# D_INPUT.net
KiCad netlist of a schematic drawn in Altium Designer
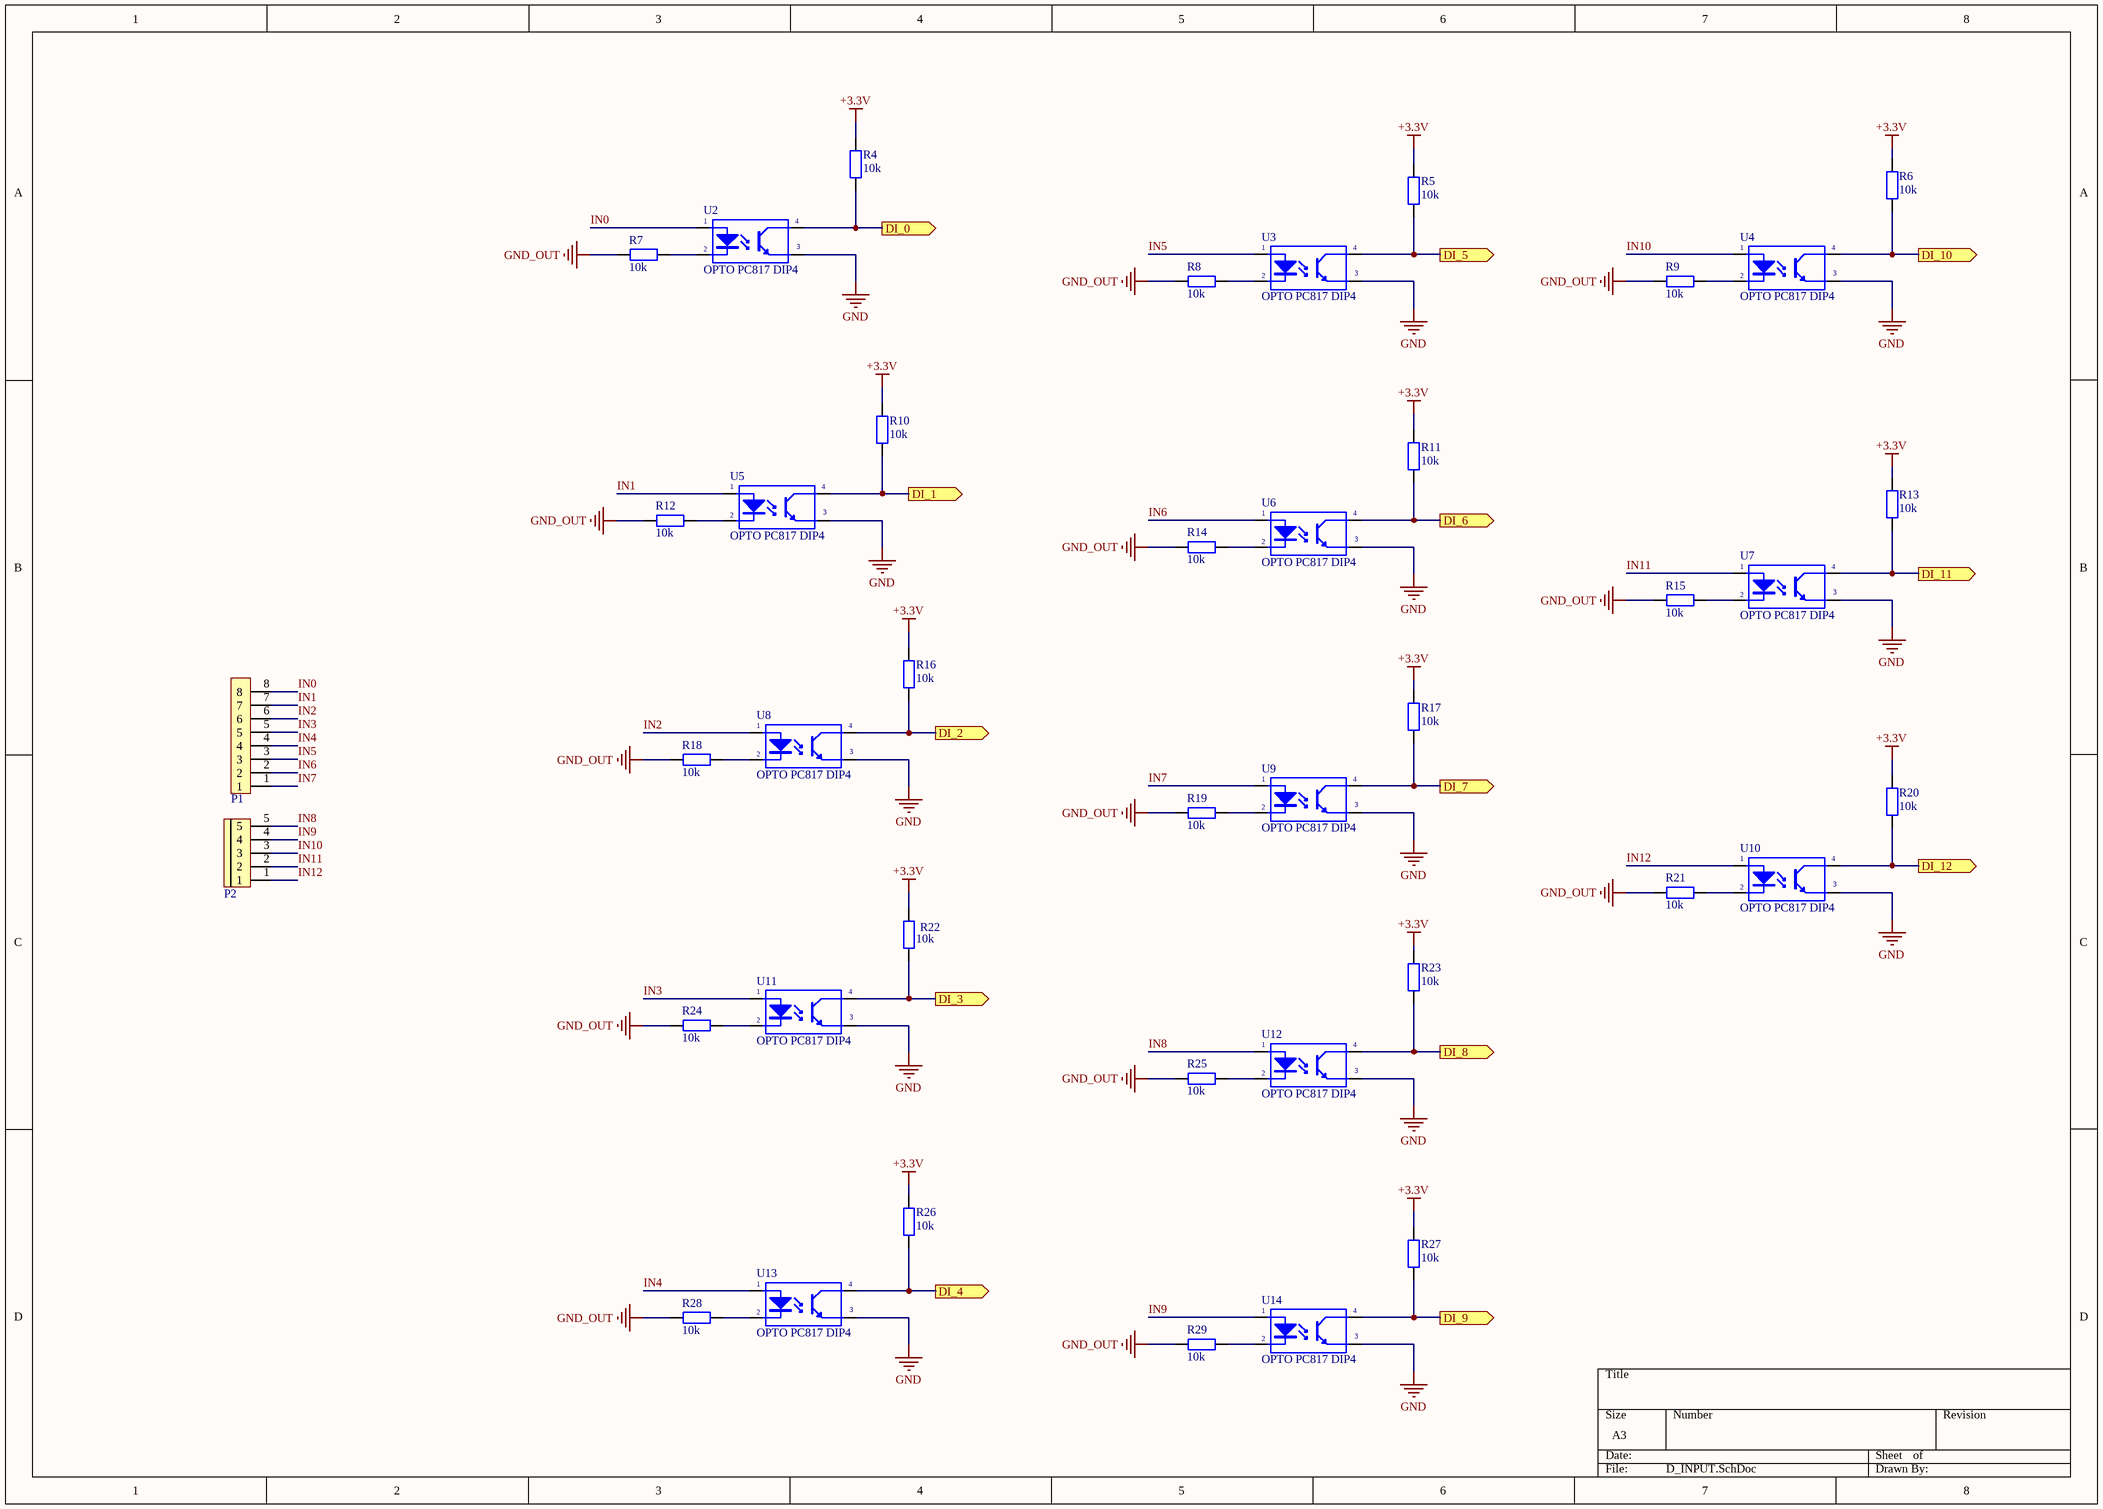
[diagram p0: D_INPUT.SchDoc]

(export (version "E")
  (design (tool "Eeschema 10.0.6"))
  (components
    (comp (ref "P1")
      (value "CON 8 EDG5.08")
      (footprint "CON 8 8EDG5.08")
      (description "Cắm")
      (libsource (lib "Altium_Lib_by_KhueNguyenCreator") (part "CON 8 EDG5.08"))
    )
    (comp (ref "P2")
      (value "CON 5 EDG5.08")
      (footprint "CON 5 5EDG5.08")
      (description "Cắm")
      (libsource (lib "Altium_Lib_by_KhueNguyenCreator") (part "CON 5 EDG5.08"))
    )
    (comp (ref "R4")
      (value "10k")
      (footprint "tro smd 0805")
      (description "Dán")
      (libsource (lib "Altium_Lib_by_KhueNguyenCreator") (part "Tro 0805 1% 10k"))
    )
    (comp (ref "R5")
      (value "10k")
      (footprint "tro smd 0805")
      (description "Dán")
      (libsource (lib "Altium_Lib_by_KhueNguyenCreator") (part "Tro 0805 1% 10k"))
    )
    (comp (ref "R6")
      (value "10k")
      (footprint "tro smd 0805")
      (description "Dán")
      (libsource (lib "Altium_Lib_by_KhueNguyenCreator") (part "Tro 0805 1% 10k"))
    )
    (comp (ref "R7")
      (value "10k")
      (footprint "tro smd 0805")
      (description "Dán")
      (libsource (lib "Altium_Lib_by_KhueNguyenCreator") (part "Tro 0805 1% 10k"))
    )
    (comp (ref "R8")
      (value "10k")
      (footprint "tro smd 0805")
      (description "Dán")
      (libsource (lib "Altium_Lib_by_KhueNguyenCreator") (part "Tro 0805 1% 10k"))
    )
    (comp (ref "R9")
      (value "10k")
      (footprint "tro smd 0805")
      (description "Dán")
      (libsource (lib "Altium_Lib_by_KhueNguyenCreator") (part "Tro 0805 1% 10k"))
    )
    (comp (ref "R10")
      (value "10k")
      (footprint "tro smd 0805")
      (description "Dán")
      (libsource (lib "Altium_Lib_by_KhueNguyenCreator") (part "Tro 0805 1% 10k"))
    )
    (comp (ref "R11")
      (value "10k")
      (footprint "tro smd 0805")
      (description "Dán")
      (libsource (lib "Altium_Lib_by_KhueNguyenCreator") (part "Tro 0805 1% 10k"))
    )
    (comp (ref "R12")
      (value "10k")
      (footprint "tro smd 0805")
      (description "Dán")
      (libsource (lib "Altium_Lib_by_KhueNguyenCreator") (part "Tro 0805 1% 10k"))
    )
    (comp (ref "R13")
      (value "10k")
      (footprint "tro smd 0805")
      (description "Dán")
      (libsource (lib "Altium_Lib_by_KhueNguyenCreator") (part "Tro 0805 1% 10k"))
    )
    (comp (ref "R14")
      (value "10k")
      (footprint "tro smd 0805")
      (description "Dán")
      (libsource (lib "Altium_Lib_by_KhueNguyenCreator") (part "Tro 0805 1% 10k"))
    )
    (comp (ref "R15")
      (value "10k")
      (footprint "tro smd 0805")
      (description "Dán")
      (libsource (lib "Altium_Lib_by_KhueNguyenCreator") (part "Tro 0805 1% 10k"))
    )
    (comp (ref "R16")
      (value "10k")
      (footprint "tro smd 0805")
      (description "Dán")
      (libsource (lib "Altium_Lib_by_KhueNguyenCreator") (part "Tro 0805 1% 10k"))
    )
    (comp (ref "R17")
      (value "10k")
      (footprint "tro smd 0805")
      (description "Dán")
      (libsource (lib "Altium_Lib_by_KhueNguyenCreator") (part "Tro 0805 1% 10k"))
    )
    (comp (ref "R18")
      (value "10k")
      (footprint "tro smd 0805")
      (description "Dán")
      (libsource (lib "Altium_Lib_by_KhueNguyenCreator") (part "Tro 0805 1% 10k"))
    )
    (comp (ref "R19")
      (value "10k")
      (footprint "tro smd 0805")
      (description "Dán")
      (libsource (lib "Altium_Lib_by_KhueNguyenCreator") (part "Tro 0805 1% 10k"))
    )
    (comp (ref "R20")
      (value "10k")
      (footprint "tro smd 0805")
      (description "Dán")
      (libsource (lib "Altium_Lib_by_KhueNguyenCreator") (part "Tro 0805 1% 10k"))
    )
    (comp (ref "R21")
      (value "10k")
      (footprint "tro smd 0805")
      (description "Dán")
      (libsource (lib "Altium_Lib_by_KhueNguyenCreator") (part "Tro 0805 1% 10k"))
    )
    (comp (ref "R22")
      (value "10k")
      (footprint "tro smd 0805")
      (description "Dán")
      (libsource (lib "Altium_Lib_by_KhueNguyenCreator") (part "Tro 0805 1% 10k"))
    )
    (comp (ref "R23")
      (value "10k")
      (footprint "tro smd 0805")
      (description "Dán")
      (libsource (lib "Altium_Lib_by_KhueNguyenCreator") (part "Tro 0805 1% 10k"))
    )
    (comp (ref "R24")
      (value "10k")
      (footprint "tro smd 0805")
      (description "Dán")
      (libsource (lib "Altium_Lib_by_KhueNguyenCreator") (part "Tro 0805 1% 10k"))
    )
    (comp (ref "R25")
      (value "10k")
      (footprint "tro smd 0805")
      (description "Dán")
      (libsource (lib "Altium_Lib_by_KhueNguyenCreator") (part "Tro 0805 1% 10k"))
    )
    (comp (ref "R26")
      (value "10k")
      (footprint "tro smd 0805")
      (description "Dán")
      (libsource (lib "Altium_Lib_by_KhueNguyenCreator") (part "Tro 0805 1% 10k"))
    )
    (comp (ref "R27")
      (value "10k")
      (footprint "tro smd 0805")
      (description "Dán")
      (libsource (lib "Altium_Lib_by_KhueNguyenCreator") (part "Tro 0805 1% 10k"))
    )
    (comp (ref "R28")
      (value "10k")
      (footprint "tro smd 0805")
      (description "Dán")
      (libsource (lib "Altium_Lib_by_KhueNguyenCreator") (part "Tro 0805 1% 10k"))
    )
    (comp (ref "R29")
      (value "10k")
      (footprint "tro smd 0805")
      (description "Dán")
      (libsource (lib "Altium_Lib_by_KhueNguyenCreator") (part "Tro 0805 1% 10k"))
    )
    (comp (ref "U2")
      (value "OPTO PC817 DIP4")
      (footprint "DIP4")
      (description "Single Opto")
      (libsource (lib "Altium_Lib_by_KhueNguyenCreator") (part "OPTO PC817 DIP4"))
    )
    (comp (ref "U3")
      (value "OPTO PC817 DIP4")
      (footprint "DIP4")
      (description "Single Opto")
      (libsource (lib "Altium_Lib_by_KhueNguyenCreator") (part "OPTO PC817 DIP4"))
    )
    (comp (ref "U4")
      (value "OPTO PC817 DIP4")
      (footprint "DIP4")
      (description "Single Opto")
      (libsource (lib "Altium_Lib_by_KhueNguyenCreator") (part "OPTO PC817 DIP4"))
    )
    (comp (ref "U5")
      (value "OPTO PC817 DIP4")
      (footprint "DIP4")
      (description "Single Opto")
      (libsource (lib "Altium_Lib_by_KhueNguyenCreator") (part "OPTO PC817 DIP4"))
    )
    (comp (ref "U6")
      (value "OPTO PC817 DIP4")
      (footprint "DIP4")
      (description "Single Opto")
      (libsource (lib "Altium_Lib_by_KhueNguyenCreator") (part "OPTO PC817 DIP4"))
    )
    (comp (ref "U7")
      (value "OPTO PC817 DIP4")
      (footprint "DIP4")
      (description "Single Opto")
      (libsource (lib "Altium_Lib_by_KhueNguyenCreator") (part "OPTO PC817 DIP4"))
    )
    (comp (ref "U8")
      (value "OPTO PC817 DIP4")
      (footprint "DIP4")
      (description "Single Opto")
      (libsource (lib "Altium_Lib_by_KhueNguyenCreator") (part "OPTO PC817 DIP4"))
    )
    (comp (ref "U9")
      (value "OPTO PC817 DIP4")
      (footprint "DIP4")
      (description "Single Opto")
      (libsource (lib "Altium_Lib_by_KhueNguyenCreator") (part "OPTO PC817 DIP4"))
    )
    (comp (ref "U10")
      (value "OPTO PC817 DIP4")
      (footprint "DIP4")
      (description "Single Opto")
      (libsource (lib "Altium_Lib_by_KhueNguyenCreator") (part "OPTO PC817 DIP4"))
    )
    (comp (ref "U11")
      (value "OPTO PC817 DIP4")
      (footprint "DIP4")
      (description "Single Opto")
      (libsource (lib "Altium_Lib_by_KhueNguyenCreator") (part "OPTO PC817 DIP4"))
    )
    (comp (ref "U12")
      (value "OPTO PC817 DIP4")
      (footprint "DIP4")
      (description "Single Opto")
      (libsource (lib "Altium_Lib_by_KhueNguyenCreator") (part "OPTO PC817 DIP4"))
    )
    (comp (ref "U13")
      (value "OPTO PC817 DIP4")
      (footprint "DIP4")
      (description "Single Opto")
      (libsource (lib "Altium_Lib_by_KhueNguyenCreator") (part "OPTO PC817 DIP4"))
    )
    (comp (ref "U14")
      (value "OPTO PC817 DIP4")
      (footprint "DIP4")
      (description "Single Opto")
      (libsource (lib "Altium_Lib_by_KhueNguyenCreator") (part "OPTO PC817 DIP4"))
    )
  )
  (nets
    (net (code "1") (name "+3.3V") (class "Default")
      (node (ref "R10") (pin "2") (pinfunction "2_2") (pintype "passive"))
      (node (ref "R11") (pin "2") (pinfunction "2_2") (pintype "passive"))
      (node (ref "R13") (pin "2") (pinfunction "2_2") (pintype "passive"))
      (node (ref "R16") (pin "2") (pinfunction "2_2") (pintype "passive"))
      (node (ref "R17") (pin "2") (pinfunction "2_2") (pintype "passive"))
      (node (ref "R20") (pin "2") (pinfunction "2_2") (pintype "passive"))
      (node (ref "R22") (pin "2") (pinfunction "2_2") (pintype "passive"))
      (node (ref "R23") (pin "2") (pinfunction "2_2") (pintype "passive"))
      (node (ref "R26") (pin "2") (pinfunction "2_2") (pintype "passive"))
      (node (ref "R27") (pin "2") (pinfunction "2_2") (pintype "passive"))
      (node (ref "R4") (pin "2") (pinfunction "2_2") (pintype "passive"))
      (node (ref "R5") (pin "2") (pinfunction "2_2") (pintype "passive"))
      (node (ref "R6") (pin "2") (pinfunction "2_2") (pintype "passive"))
    )
    (net (code "2") (name "/DI_0") (class "Default")
      (node (ref "R4") (pin "1") (pinfunction "1_1") (pintype "passive"))
      (node (ref "U2") (pin "4") (pinfunction "C_4") (pintype "passive"))
    )
    (net (code "3") (name "/DI_1") (class "Default")
      (node (ref "R10") (pin "1") (pinfunction "1_1") (pintype "passive"))
      (node (ref "U5") (pin "4") (pinfunction "C_4") (pintype "passive"))
    )
    (net (code "4") (name "/DI_2") (class "Default")
      (node (ref "R16") (pin "1") (pinfunction "1_1") (pintype "passive"))
      (node (ref "U8") (pin "4") (pinfunction "C_4") (pintype "passive"))
    )
    (net (code "5") (name "/DI_3") (class "Default")
      (node (ref "R22") (pin "1") (pinfunction "1_1") (pintype "passive"))
      (node (ref "U11") (pin "4") (pinfunction "C_4") (pintype "passive"))
    )
    (net (code "6") (name "/DI_4") (class "Default")
      (node (ref "R26") (pin "1") (pinfunction "1_1") (pintype "passive"))
      (node (ref "U13") (pin "4") (pinfunction "C_4") (pintype "passive"))
    )
    (net (code "7") (name "/DI_5") (class "Default")
      (node (ref "R5") (pin "1") (pinfunction "1_1") (pintype "passive"))
      (node (ref "U3") (pin "4") (pinfunction "C_4") (pintype "passive"))
    )
    (net (code "8") (name "/DI_6") (class "Default")
      (node (ref "R11") (pin "1") (pinfunction "1_1") (pintype "passive"))
      (node (ref "U6") (pin "4") (pinfunction "C_4") (pintype "passive"))
    )
    (net (code "9") (name "/DI_7") (class "Default")
      (node (ref "R17") (pin "1") (pinfunction "1_1") (pintype "passive"))
      (node (ref "U9") (pin "4") (pinfunction "C_4") (pintype "passive"))
    )
    (net (code "10") (name "/DI_8") (class "Default")
      (node (ref "R23") (pin "1") (pinfunction "1_1") (pintype "passive"))
      (node (ref "U12") (pin "4") (pinfunction "C_4") (pintype "passive"))
    )
    (net (code "11") (name "/DI_9") (class "Default")
      (node (ref "R27") (pin "1") (pinfunction "1_1") (pintype "passive"))
      (node (ref "U14") (pin "4") (pinfunction "C_4") (pintype "passive"))
    )
    (net (code "12") (name "/DI_10") (class "Default")
      (node (ref "R6") (pin "1") (pinfunction "1_1") (pintype "passive"))
      (node (ref "U4") (pin "4") (pinfunction "C_4") (pintype "passive"))
    )
    (net (code "13") (name "/DI_11") (class "Default")
      (node (ref "R13") (pin "1") (pinfunction "1_1") (pintype "passive"))
      (node (ref "U7") (pin "4") (pinfunction "C_4") (pintype "passive"))
    )
    (net (code "14") (name "/DI_12") (class "Default")
      (node (ref "R20") (pin "1") (pinfunction "1_1") (pintype "passive"))
      (node (ref "U10") (pin "4") (pinfunction "C_4") (pintype "passive"))
    )
    (net (code "15") (name "/IN0") (class "Default")
      (node (ref "P1") (pin "8") (pinfunction "8_8") (pintype "passive"))
      (node (ref "U2") (pin "1") (pinfunction "A_1") (pintype "passive"))
    )
    (net (code "16") (name "/IN1") (class "Default")
      (node (ref "P1") (pin "7") (pinfunction "7_7") (pintype "passive"))
      (node (ref "U5") (pin "1") (pinfunction "A_1") (pintype "passive"))
    )
    (net (code "17") (name "/IN2") (class "Default")
      (node (ref "P1") (pin "6") (pinfunction "6_6") (pintype "passive"))
      (node (ref "U8") (pin "1") (pinfunction "A_1") (pintype "passive"))
    )
    (net (code "18") (name "/IN3") (class "Default")
      (node (ref "P1") (pin "5") (pinfunction "5_5") (pintype "passive"))
      (node (ref "U11") (pin "1") (pinfunction "A_1") (pintype "passive"))
    )
    (net (code "19") (name "/IN4") (class "Default")
      (node (ref "P1") (pin "4") (pinfunction "4_4") (pintype "passive"))
      (node (ref "U13") (pin "1") (pinfunction "A_1") (pintype "passive"))
    )
    (net (code "20") (name "/IN5") (class "Default")
      (node (ref "P1") (pin "3") (pinfunction "3_3") (pintype "passive"))
      (node (ref "U3") (pin "1") (pinfunction "A_1") (pintype "passive"))
    )
    (net (code "21") (name "/IN6") (class "Default")
      (node (ref "P1") (pin "2") (pinfunction "2_2") (pintype "passive"))
      (node (ref "U6") (pin "1") (pinfunction "A_1") (pintype "passive"))
    )
    (net (code "22") (name "/IN7") (class "Default")
      (node (ref "P1") (pin "1") (pinfunction "1_1") (pintype "passive"))
      (node (ref "U9") (pin "1") (pinfunction "A_1") (pintype "passive"))
    )
    (net (code "23") (name "/IN8") (class "Default")
      (node (ref "P2") (pin "5") (pinfunction "5_5") (pintype "passive"))
      (node (ref "U12") (pin "1") (pinfunction "A_1") (pintype "passive"))
    )
    (net (code "24") (name "/IN9") (class "Default")
      (node (ref "P2") (pin "4") (pinfunction "4_4") (pintype "passive"))
      (node (ref "U14") (pin "1") (pinfunction "A_1") (pintype "passive"))
    )
    (net (code "25") (name "/IN10") (class "Default")
      (node (ref "P2") (pin "3") (pinfunction "3_3") (pintype "passive"))
      (node (ref "U4") (pin "1") (pinfunction "A_1") (pintype "passive"))
    )
    (net (code "26") (name "/IN11") (class "Default")
      (node (ref "P2") (pin "2") (pinfunction "2_2") (pintype "passive"))
      (node (ref "U7") (pin "1") (pinfunction "A_1") (pintype "passive"))
    )
    (net (code "27") (name "/IN12") (class "Default")
      (node (ref "P2") (pin "1") (pinfunction "1_1") (pintype "passive"))
      (node (ref "U10") (pin "1") (pinfunction "A_1") (pintype "passive"))
    )
    (net (code "28") (name "GND") (class "Default")
      (node (ref "U10") (pin "3") (pinfunction "E_3") (pintype "passive"))
      (node (ref "U11") (pin "3") (pinfunction "E_3") (pintype "passive"))
      (node (ref "U12") (pin "3") (pinfunction "E_3") (pintype "passive"))
      (node (ref "U13") (pin "3") (pinfunction "E_3") (pintype "passive"))
      (node (ref "U14") (pin "3") (pinfunction "E_3") (pintype "passive"))
      (node (ref "U2") (pin "3") (pinfunction "E_3") (pintype "passive"))
      (node (ref "U3") (pin "3") (pinfunction "E_3") (pintype "passive"))
      (node (ref "U4") (pin "3") (pinfunction "E_3") (pintype "passive"))
      (node (ref "U5") (pin "3") (pinfunction "E_3") (pintype "passive"))
      (node (ref "U6") (pin "3") (pinfunction "E_3") (pintype "passive"))
      (node (ref "U7") (pin "3") (pinfunction "E_3") (pintype "passive"))
      (node (ref "U8") (pin "3") (pinfunction "E_3") (pintype "passive"))
      (node (ref "U9") (pin "3") (pinfunction "E_3") (pintype "passive"))
    )
    (net (code "29") (name "GND_OUT") (class "Default")
      (node (ref "R12") (pin "1") (pinfunction "1_1") (pintype "passive"))
      (node (ref "R14") (pin "1") (pinfunction "1_1") (pintype "passive"))
      (node (ref "R15") (pin "1") (pinfunction "1_1") (pintype "passive"))
      (node (ref "R18") (pin "1") (pinfunction "1_1") (pintype "passive"))
      (node (ref "R19") (pin "1") (pinfunction "1_1") (pintype "passive"))
      (node (ref "R21") (pin "1") (pinfunction "1_1") (pintype "passive"))
      (node (ref "R24") (pin "1") (pinfunction "1_1") (pintype "passive"))
      (node (ref "R25") (pin "1") (pinfunction "1_1") (pintype "passive"))
      (node (ref "R28") (pin "1") (pinfunction "1_1") (pintype "passive"))
      (node (ref "R29") (pin "1") (pinfunction "1_1") (pintype "passive"))
      (node (ref "R7") (pin "1") (pinfunction "1_1") (pintype "passive"))
      (node (ref "R8") (pin "1") (pinfunction "1_1") (pintype "passive"))
      (node (ref "R9") (pin "1") (pinfunction "1_1") (pintype "passive"))
    )
    (net (code "30") (name "Net-(U2-K)") (class "Default")
      (node (ref "R7") (pin "2") (pinfunction "2_2") (pintype "passive"))
      (node (ref "U2") (pin "2") (pinfunction "K_2") (pintype "passive"))
    )
    (net (code "31") (name "Net-(U3-K)") (class "Default")
      (node (ref "R8") (pin "2") (pinfunction "2_2") (pintype "passive"))
      (node (ref "U3") (pin "2") (pinfunction "K_2") (pintype "passive"))
    )
    (net (code "32") (name "Net-(U4-K)") (class "Default")
      (node (ref "R9") (pin "2") (pinfunction "2_2") (pintype "passive"))
      (node (ref "U4") (pin "2") (pinfunction "K_2") (pintype "passive"))
    )
    (net (code "33") (name "Net-(U5-K)") (class "Default")
      (node (ref "R12") (pin "2") (pinfunction "2_2") (pintype "passive"))
      (node (ref "U5") (pin "2") (pinfunction "K_2") (pintype "passive"))
    )
    (net (code "34") (name "Net-(U6-K)") (class "Default")
      (node (ref "R14") (pin "2") (pinfunction "2_2") (pintype "passive"))
      (node (ref "U6") (pin "2") (pinfunction "K_2") (pintype "passive"))
    )
    (net (code "35") (name "Net-(U7-K)") (class "Default")
      (node (ref "R15") (pin "2") (pinfunction "2_2") (pintype "passive"))
      (node (ref "U7") (pin "2") (pinfunction "K_2") (pintype "passive"))
    )
    (net (code "36") (name "Net-(U8-K)") (class "Default")
      (node (ref "R18") (pin "2") (pinfunction "2_2") (pintype "passive"))
      (node (ref "U8") (pin "2") (pinfunction "K_2") (pintype "passive"))
    )
    (net (code "37") (name "Net-(U9-K)") (class "Default")
      (node (ref "R19") (pin "2") (pinfunction "2_2") (pintype "passive"))
      (node (ref "U9") (pin "2") (pinfunction "K_2") (pintype "passive"))
    )
    (net (code "38") (name "Net-(U10-K)") (class "Default")
      (node (ref "R21") (pin "2") (pinfunction "2_2") (pintype "passive"))
      (node (ref "U10") (pin "2") (pinfunction "K_2") (pintype "passive"))
    )
    (net (code "39") (name "Net-(U11-K)") (class "Default")
      (node (ref "R24") (pin "2") (pinfunction "2_2") (pintype "passive"))
      (node (ref "U11") (pin "2") (pinfunction "K_2") (pintype "passive"))
    )
    (net (code "40") (name "Net-(U12-K)") (class "Default")
      (node (ref "R25") (pin "2") (pinfunction "2_2") (pintype "passive"))
      (node (ref "U12") (pin "2") (pinfunction "K_2") (pintype "passive"))
    )
    (net (code "41") (name "Net-(U13-K)") (class "Default")
      (node (ref "R28") (pin "2") (pinfunction "2_2") (pintype "passive"))
      (node (ref "U13") (pin "2") (pinfunction "K_2") (pintype "passive"))
    )
    (net (code "42") (name "Net-(U14-K)") (class "Default")
      (node (ref "R29") (pin "2") (pinfunction "2_2") (pintype "passive"))
      (node (ref "U14") (pin "2") (pinfunction "K_2") (pintype "passive"))
    )
  )
)
